# PowerModule.net
KiCad netlist of a schematic drawn in Altium Designer
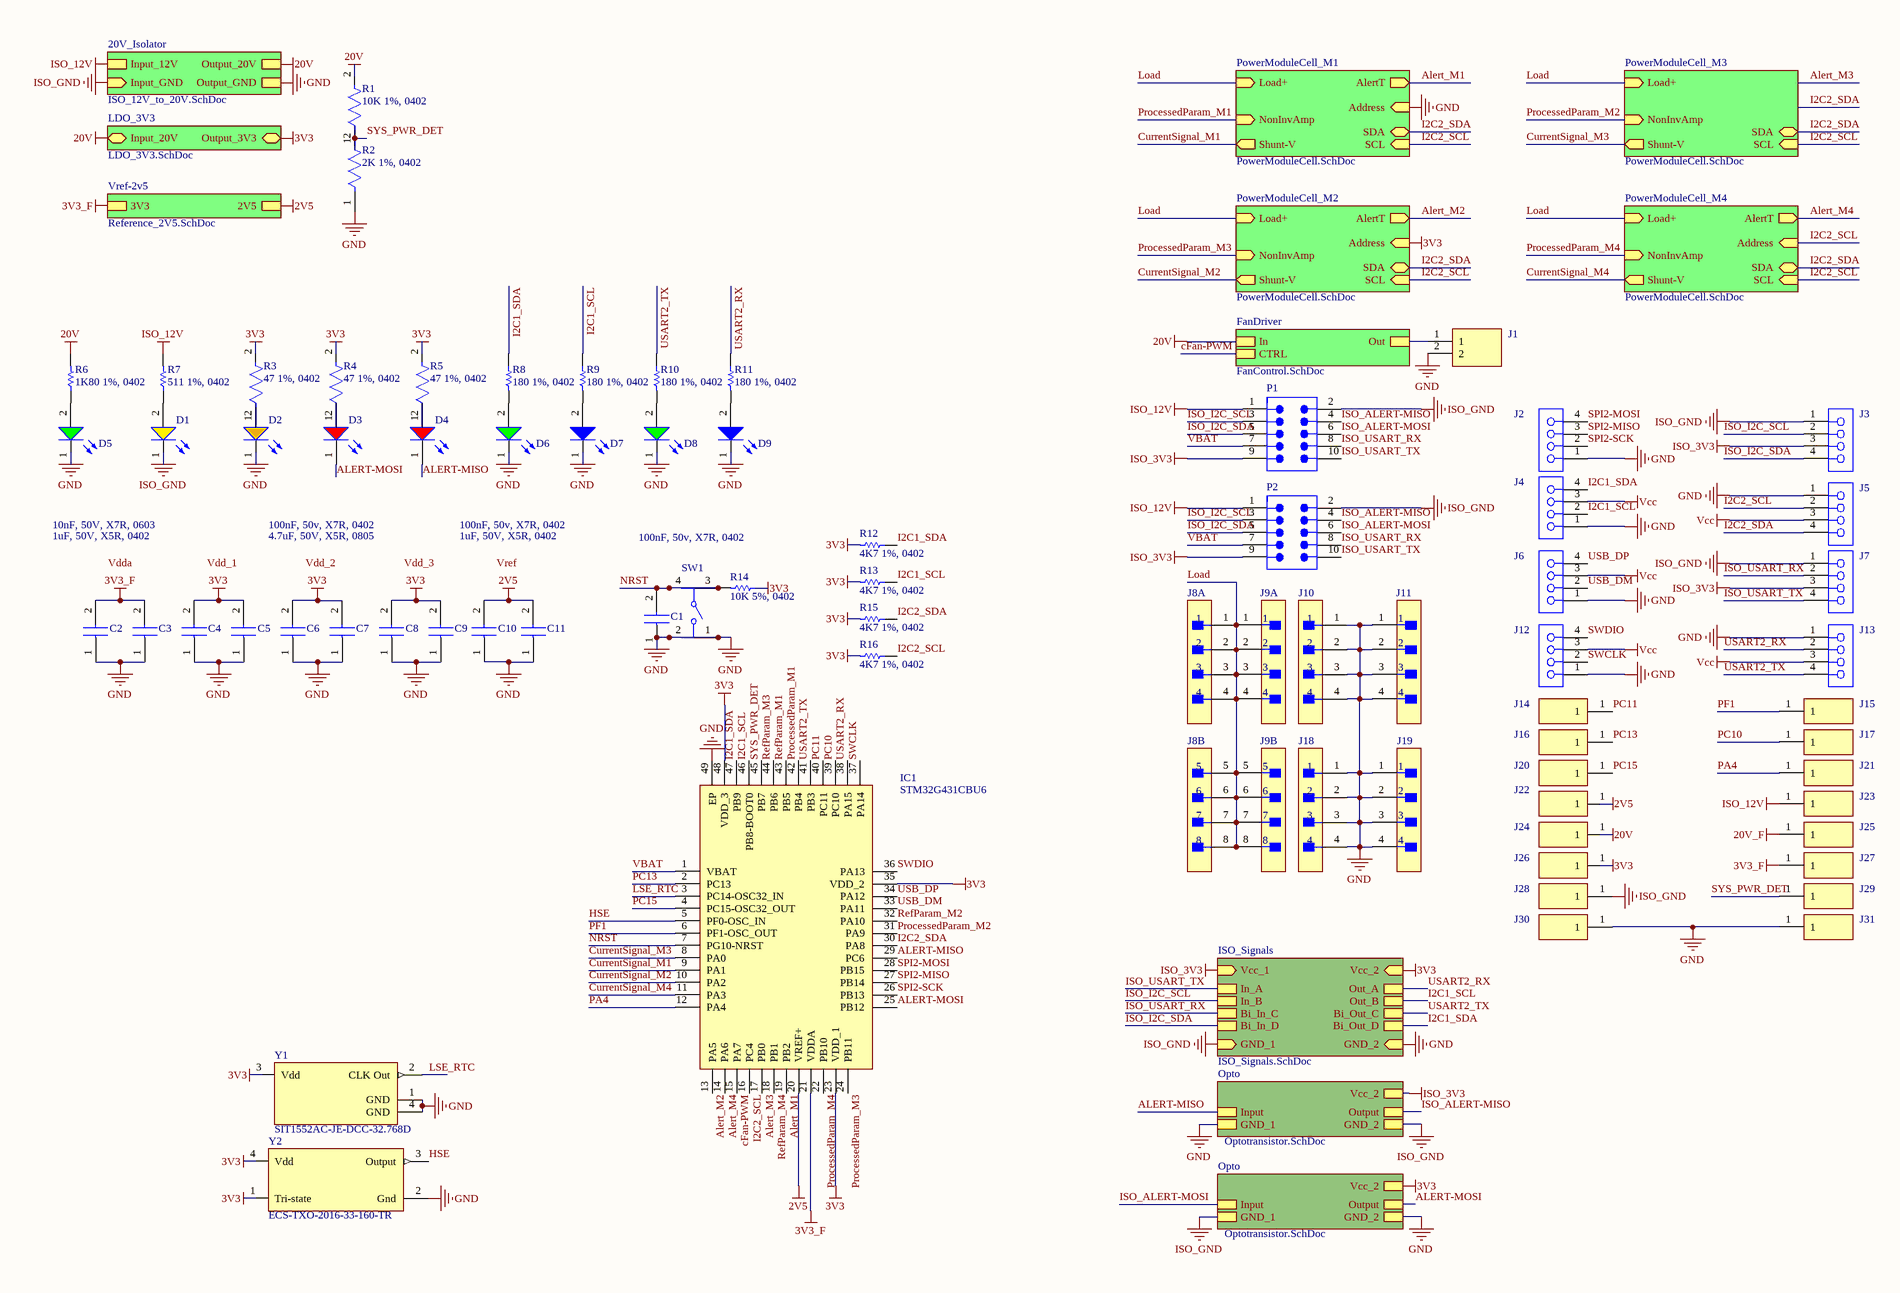
[diagram p0: PowerModule.SchDoc, left]
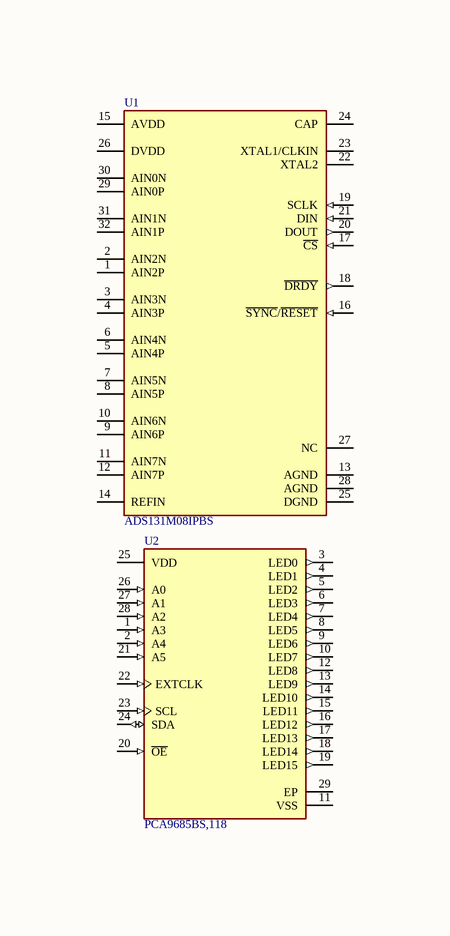
[diagram p1: PowerModule.SchDoc, middle]
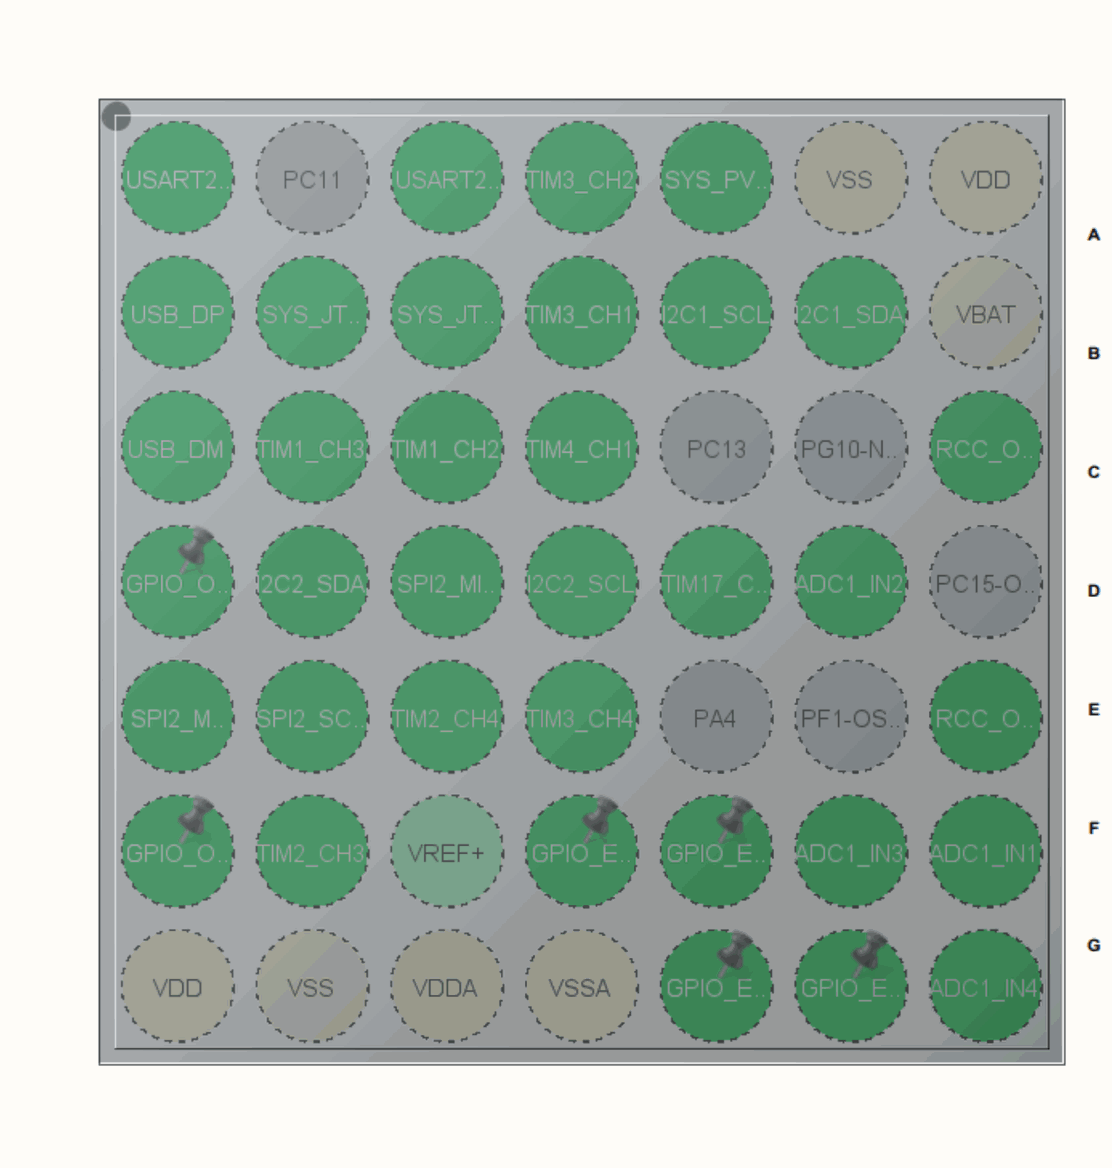
[diagram p2: PowerModule.SchDoc, right]

(export (version "E")
  (design (tool "Eeschema 10.0.6"))
  (components
    (comp (ref "C1")
      (value "100nF, 50v, X7R, 0402")
      (footprint "SamacSys:CAPC2012X88N")
      (description "Capacitor")
      (fields
        (field (name "MANUFACTURER_PART_NUMBER") "C0805C104M5RAC")
        (field (name "MOUSER PART NUMBER") "80-C0805C104M5RAC")
      )
      (libsource (lib "*") (part "C0805C104M5RAC"))
    )
    (comp (ref "C2")
      (value "10nF, 50V, X7R, 0603")
      (footprint "SamacSys:CAPC1608X87N")
      (description "Capacitor")
      (fields
        (field (name "MANUFACTURER_PART_NUMBER") "C0603C103J5RAC")
        (field (name "MOUSER PART NUMBER") "80-C0603C103J5RAC")
      )
      (libsource (lib "*") (part "C0603C103J5RAC"))
    )
    (comp (ref "C3")
      (value "1uF, 50V, X5R, 0402")
      (footprint "SamacSys:GRM15x")
      (description "Capacitor")
      (fields
        (field (name "MANUFACTURER_PART_NUMBER") "GRM155R61H105KE05J")
        (field (name "MOUSER PART NUMBER") "81-GRM155R61H105KE5J")
      )
      (libsource (lib "*") (part "GRM155R61H105KE05J"))
    )
    (comp (ref "C4")
      (value "100nF, 50v, X7R, 0402")
      (footprint "SamacSys:CAPC2012X88N")
      (description "Capacitor")
      (fields
        (field (name "MANUFACTURER_PART_NUMBER") "C0805C104M5RAC")
        (field (name "MOUSER PART NUMBER") "80-C0805C104M5RAC")
      )
      (libsource (lib "*") (part "C0805C104M5RAC"))
    )
    (comp (ref "C5")
      (value "4.7uF, 50V, X5R, 0805")
      (footprint "SamacSys:CAPC2012X145N")
      (description "Capacitor")
      (fields
        (field (name "MANUFACTURER_PART_NUMBER") "GRM21BR61H475ME51L")
        (field (name "MOUSER PART NUMBER") "81-GRM21BR61H475M51L")
      )
      (libsource (lib "*") (part "GRM21BR61H475ME51L"))
    )
    (comp (ref "C6")
      (value "100nF, 50v, X7R, 0402")
      (footprint "SamacSys:CAPC2012X88N")
      (description "Capacitor")
      (fields
        (field (name "MANUFACTURER_PART_NUMBER") "C0805C104M5RAC")
        (field (name "MOUSER PART NUMBER") "80-C0805C104M5RAC")
      )
      (libsource (lib "*") (part "C0805C104M5RAC"))
    )
    (comp (ref "C7")
      (value "4.7uF, 50V, X5R, 0805")
      (footprint "SamacSys:CAPC2012X145N")
      (description "Capacitor")
      (fields
        (field (name "MANUFACTURER_PART_NUMBER") "GRM21BR61H475ME51L")
        (field (name "MOUSER PART NUMBER") "81-GRM21BR61H475M51L")
      )
      (libsource (lib "*") (part "GRM21BR61H475ME51L"))
    )
    (comp (ref "C8")
      (value "100nF, 50v, X7R, 0402")
      (footprint "SamacSys:CAPC2012X88N")
      (description "Capacitor")
      (fields
        (field (name "MANUFACTURER_PART_NUMBER") "C0805C104M5RAC")
        (field (name "MOUSER PART NUMBER") "80-C0805C104M5RAC")
      )
      (libsource (lib "*") (part "C0805C104M5RAC"))
    )
    (comp (ref "C9")
      (value "4.7uF, 50V, X5R, 0805")
      (footprint "SamacSys:CAPC2012X145N")
      (description "Capacitor")
      (fields
        (field (name "MANUFACTURER_PART_NUMBER") "GRM21BR61H475ME51L")
        (field (name "MOUSER PART NUMBER") "81-GRM21BR61H475M51L")
      )
      (libsource (lib "*") (part "GRM21BR61H475ME51L"))
    )
    (comp (ref "C10")
      (value "100nF, 50v, X7R, 0402")
      (footprint "SamacSys:CAPC2012X88N")
      (description "Capacitor")
      (fields
        (field (name "MANUFACTURER_PART_NUMBER") "C0805C104M5RAC")
        (field (name "MOUSER PART NUMBER") "80-C0805C104M5RAC")
      )
      (libsource (lib "*") (part "C0805C104M5RAC"))
    )
    (comp (ref "C11")
      (value "1uF, 50V, X5R, 0402")
      (footprint "SamacSys:GRM15x")
      (description "Capacitor")
      (fields
        (field (name "MANUFACTURER_PART_NUMBER") "GRM155R61H105KE05J")
        (field (name "MOUSER PART NUMBER") "81-GRM155R61H105KE5J")
      )
      (libsource (lib "*") (part "GRM155R61H105KE05J"))
    )
    (comp (ref "D1")
      (value "150060YS75000")
      (footprint "WL-SMCW_0603_150060xx75000")
      (description "WL-SMCW SMT Mono-Color Chip LED Waterclear")
      (libsource (lib "Altium Content Vault") (part "LED_Yellow_2A-1K"))
    )
    (comp (ref "D2")
      (value "150060AS75000")
      (footprint "WL-SMCW_0603_150060xx75000")
      (description "WL-SMCW SMT Mono-Color Chip LED Waterclear")
      (libsource (lib "Altium Content Vault") (part "LED_Amber_2A-1K"))
    )
    (comp (ref "D3")
      (value "150060RS75000")
      (footprint "WL-SMCW_0603_150060xx75000")
      (description "LED Low-Power Uni-Color Red 630nm 2V 2-Pin Chip 0603(1608Metric) T/R")
      (libsource (lib "Altium Content Vault") (part "LED_Red_2A-1K"))
    )
    (comp (ref "D4")
      (value "150060RS75000")
      (footprint "WL-SMCW_0603_150060xx75000")
      (description "LED Low-Power Uni-Color Red 630nm 2V 2-Pin Chip 0603(1608Metric) T/R")
      (libsource (lib "Altium Content Vault") (part "LED_Red_2A-1K"))
    )
    (comp (ref "D5")
      (value "150060GS75000")
      (footprint "WL-SMCW_0603_150060xx75000")
      (description "430mcd Colorless transparence 520nm Emerald 140° LED0603 Light Emitting Diodes (LED) ROHS")
      (libsource (lib "Altium Content Vault") (part "LED_Green_2A-1K"))
    )
    (comp (ref "D6")
      (value "150060GS75000")
      (footprint "WL-SMCW_0603_150060xx75000")
      (description "430mcd Colorless transparence 520nm Emerald 140° LED0603 Light Emitting Diodes (LED) ROHS")
      (libsource (lib "Altium Content Vault") (part "LED_Green_2A-1K"))
    )
    (comp (ref "D7")
      (value "150060BS75000")
      (footprint "WL-SMCW_0603_150060xx75000")
      (description "Led, Blue, 470 Nm, 3.2 V, 30 Ma, 145 Mcd Rohs Compliant: Yes")
      (libsource (lib "Altium Content Vault") (part "LED_Blue_2A-1K"))
    )
    (comp (ref "D8")
      (value "150060GS75000")
      (footprint "WL-SMCW_0603_150060xx75000")
      (description "430mcd Colorless transparence 520nm Emerald 140° LED0603 Light Emitting Diodes (LED) ROHS")
      (libsource (lib "Altium Content Vault") (part "LED_Green_2A-1K"))
    )
    (comp (ref "D9")
      (value "150060BS75000")
      (footprint "WL-SMCW_0603_150060xx75000")
      (description "Led, Blue, 470 Nm, 3.2 V, 30 Ma, 145 Mcd Rohs Compliant: Yes")
      (libsource (lib "Altium Content Vault") (part "LED_Blue_2A-1K"))
    )
    (comp (ref "IC1")
      (value "STM32G431CBU6")
      (footprint "SamacSys:QFN50P700X700X65-49N-D")
      (description "Integrated Circuit")
      (fields (field (name "MOUSER PART NUMBER") "511-STM32G431CBU6"))
      (libsource (lib "*") (part "STM32G431CBU6"))
    )
    (comp (ref "J1")
      (value "1725656")
      (footprint "SamacSys:1725656")
      (description "Connector")
      (fields (field (name "MOUSER PART NUMBER") "651-1725656"))
      (libsource (lib "*") (part "1725656"))
    )
    (comp (ref "J2")
      (value "61300411821")
      (footprint "61300411821")
      (libsource (lib "Altium Content Vault") (part "Header_Female_1R_04P"))
    )
    (comp (ref "J3")
      (value "61300411821")
      (footprint "61300411821")
      (libsource (lib "Altium Content Vault") (part "Header_Female_1R_04P"))
    )
    (comp (ref "J4")
      (value "61300411821")
      (footprint "61300411821")
      (libsource (lib "Altium Content Vault") (part "Header_Female_1R_04P"))
    )
    (comp (ref "J5")
      (value "61300411821")
      (footprint "61300411821")
      (libsource (lib "Altium Content Vault") (part "Header_Female_1R_04P"))
    )
    (comp (ref "J6")
      (value "61300411821")
      (footprint "61300411821")
      (libsource (lib "Altium Content Vault") (part "Header_Female_1R_04P"))
    )
    (comp (ref "J7")
      (value "61300411821")
      (footprint "61300411821")
      (libsource (lib "Altium Content Vault") (part "Header_Female_1R_04P"))
    )
    (comp (ref "J8")
      (value "43045-0802")
      (footprint "FP-43045-0802-MFG")
      (description "CONN HEADER R/A 8POS 3MM")
      (libsource (lib "") (part "85438c39ca9ef07d43bb2e97c52bc44_1"))
    )
    (comp (ref "J9")
      (value "43045-0802")
      (footprint "FP-43045-0802-MFG")
      (description "CONN HEADER R/A 8POS 3MM")
      (libsource (lib "Altium Content Vault") (part "85438c39ca9ef07d43bb2e97c52bc44"))
    )
    (comp (ref "J10")
      (value "43045-0400")
      (footprint "FP-43045-0400-MFG")
      (description "CONN HEADER R/A 4POS 3MM")
      (fields
        (field (name "MANUFACTURER") "Molex")
        (field (name "OCTOPART") "https://octopart.com/43045-0400-molex-287063")
      )
      (libsource (lib "Altium Content Vault") (part "c01754ab0efc13afb7424b896f394ef"))
    )
    (comp (ref "J11")
      (value "43045-0400")
      (footprint "FP-43045-0400-MFG")
      (description "CONN HEADER R/A 4POS 3MM")
      (fields
        (field (name "MANUFACTURER") "Molex")
        (field (name "OCTOPART") "https://octopart.com/43045-0400-molex-287063")
      )
      (libsource (lib "") (part "c01754ab0efc13afb7424b896f394ef_1"))
    )
    (comp (ref "J12")
      (value "61300411821")
      (footprint "61300411821")
      (libsource (lib "Altium Content Vault") (part "Header_Female_1R_04P"))
    )
    (comp (ref "J13")
      (value "61300411821")
      (footprint "61300411821")
      (libsource (lib "Altium Content Vault") (part "Header_Female_1R_04P"))
    )
    (comp (ref "J14")
      (value "TestPad")
      (footprint "SamacSys:TestPad")
      (description "Connector")
      (fields
        (field (name "MANUFACTURER_PART_NUMBER") "61300111121")
        (field (name "MOUSER PART NUMBER") "710-61300111121")
      )
      (libsource (lib "") (part "61300111121_1"))
    )
    (comp (ref "J15")
      (value "TestPad")
      (footprint "SamacSys:TestPad")
      (description "Connector")
      (fields
        (field (name "MANUFACTURER_PART_NUMBER") "61300111121")
        (field (name "MOUSER PART NUMBER") "710-61300111121")
      )
      (libsource (lib "*") (part "61300111121"))
    )
    (comp (ref "J16")
      (value "TestPad")
      (footprint "SamacSys:TestPad")
      (description "Connector")
      (fields
        (field (name "MANUFACTURER_PART_NUMBER") "61300111121")
        (field (name "MOUSER PART NUMBER") "710-61300111121")
      )
      (libsource (lib "") (part "61300111121_1"))
    )
    (comp (ref "J17")
      (value "TestPad")
      (footprint "SamacSys:TestPad")
      (description "Connector")
      (fields
        (field (name "MANUFACTURER_PART_NUMBER") "61300111121")
        (field (name "MOUSER PART NUMBER") "710-61300111121")
      )
      (libsource (lib "*") (part "61300111121"))
    )
    (comp (ref "J18")
      (value "43045-0400")
      (footprint "FP-43045-0400-MFG")
      (description "CONN HEADER R/A 4POS 3MM")
      (fields
        (field (name "MANUFACTURER") "Molex")
        (field (name "OCTOPART") "https://octopart.com/43045-0400-molex-287063")
      )
      (libsource (lib "Altium Content Vault") (part "c01754ab0efc13afb7424b896f394ef"))
    )
    (comp (ref "J19")
      (value "43045-0400")
      (footprint "FP-43045-0400-MFG")
      (description "CONN HEADER R/A 4POS 3MM")
      (fields
        (field (name "MANUFACTURER") "Molex")
        (field (name "OCTOPART") "https://octopart.com/43045-0400-molex-287063")
      )
      (libsource (lib "") (part "c01754ab0efc13afb7424b896f394ef_1"))
    )
    (comp (ref "J20")
      (value "TestPad")
      (footprint "SamacSys:TestPad")
      (description "Connector")
      (fields
        (field (name "MANUFACTURER_PART_NUMBER") "61300111121")
        (field (name "MOUSER PART NUMBER") "710-61300111121")
      )
      (libsource (lib "") (part "61300111121_1"))
    )
    (comp (ref "J21")
      (value "TestPad")
      (footprint "SamacSys:TestPad")
      (description "Connector")
      (fields
        (field (name "MANUFACTURER_PART_NUMBER") "61300111121")
        (field (name "MOUSER PART NUMBER") "710-61300111121")
      )
      (libsource (lib "*") (part "61300111121"))
    )
    (comp (ref "J22")
      (value "TestPad")
      (footprint "SamacSys:TestPad")
      (description "Connector")
      (fields
        (field (name "MANUFACTURER_PART_NUMBER") "61300111121")
        (field (name "MOUSER PART NUMBER") "710-61300111121")
      )
      (libsource (lib "") (part "61300111121_1"))
    )
    (comp (ref "J23")
      (value "TestPad")
      (footprint "SamacSys:TestPad")
      (description "Connector")
      (fields
        (field (name "MANUFACTURER_PART_NUMBER") "61300111121")
        (field (name "MOUSER PART NUMBER") "710-61300111121")
      )
      (libsource (lib "*") (part "61300111121"))
    )
    (comp (ref "J24")
      (value "TestPad")
      (footprint "SamacSys:TestPad")
      (description "Connector")
      (fields
        (field (name "MANUFACTURER_PART_NUMBER") "61300111121")
        (field (name "MOUSER PART NUMBER") "710-61300111121")
      )
      (libsource (lib "") (part "61300111121_1"))
    )
    (comp (ref "J25")
      (value "TestPad")
      (footprint "SamacSys:TestPad")
      (description "Connector")
      (fields
        (field (name "MANUFACTURER_PART_NUMBER") "61300111121")
        (field (name "MOUSER PART NUMBER") "710-61300111121")
      )
      (libsource (lib "*") (part "61300111121"))
    )
    (comp (ref "J26")
      (value "TestPad")
      (footprint "SamacSys:TestPad")
      (description "Connector")
      (fields
        (field (name "MANUFACTURER_PART_NUMBER") "61300111121")
        (field (name "MOUSER PART NUMBER") "710-61300111121")
      )
      (libsource (lib "") (part "61300111121_1"))
    )
    (comp (ref "J27")
      (value "TestPad")
      (footprint "SamacSys:TestPad")
      (description "Connector")
      (fields
        (field (name "MANUFACTURER_PART_NUMBER") "61300111121")
        (field (name "MOUSER PART NUMBER") "710-61300111121")
      )
      (libsource (lib "*") (part "61300111121"))
    )
    (comp (ref "J28")
      (value "TestPad")
      (footprint "SamacSys:TestPad")
      (description "Connector")
      (fields
        (field (name "MANUFACTURER_PART_NUMBER") "61300111121")
        (field (name "MOUSER PART NUMBER") "710-61300111121")
      )
      (libsource (lib "") (part "61300111121_2"))
    )
    (comp (ref "J29")
      (value "TestPad")
      (footprint "SamacSys:TestPad")
      (description "Connector")
      (fields
        (field (name "MANUFACTURER_PART_NUMBER") "61300111121")
        (field (name "MOUSER PART NUMBER") "710-61300111121")
      )
      (libsource (lib "") (part "61300111121_3"))
    )
    (comp (ref "J30")
      (value "TestPad")
      (footprint "SamacSys:TestPad")
      (description "Connector")
      (fields
        (field (name "MANUFACTURER_PART_NUMBER") "61300111121")
        (field (name "MOUSER PART NUMBER") "710-61300111121")
      )
      (libsource (lib "") (part "61300111121_1"))
    )
    (comp (ref "J31")
      (value "TestPad")
      (footprint "SamacSys:TestPad")
      (description "Connector")
      (fields
        (field (name "MANUFACTURER_PART_NUMBER") "61300111121")
        (field (name "MOUSER PART NUMBER") "710-61300111121")
      )
      (libsource (lib "*") (part "61300111121"))
    )
    (comp (ref "P1")
      (value "61201021621")
      (footprint "61201021621")
      (libsource (lib "Altium Content Vault") (part "Header_Male_2R_10P"))
    )
    (comp (ref "P2")
      (value "61201021621")
      (footprint "61201021621")
      (libsource (lib "Altium Content Vault") (part "Header_Male_2R_10P"))
    )
    (comp (ref "R1")
      (value "10K 1%, 0402")
      (footprint "FP-ERA2A-MFG")
      (description "RES SMD 10K OHM 0.1% 1/16W 0402")
      (fields (field (name "TOLERANCE") "0.1%") (field (name "MANUFACTURER PART NUMBER") "ERA-2AEB103X"))
      (libsource (lib "Altium Content Vault") (part "1029c3af85768c4190bb7ad29bc67b5"))
    )
    (comp (ref "R2")
      (value "2K 1%, 0402")
      (footprint "FP-ERJ2RK-MFG")
      (description "RES SMD 2K OHM 1% 1/10W 0402")
      (fields (field (name "TOLERANCE") "1%"))
      (libsource (lib "Altium Content Vault") (part "1029c3af85768c4190bb7ad29bc67b5"))
    )
    (comp (ref "R3")
      (value "47 1%, 0402")
      (footprint "FP-ERJ2RK-IPC_C")
      (description "RES SMD 47 OHM 1% 1/10W 0402")
      (fields (field (name "TOLERANCE") "1%"))
      (libsource (lib "Altium Content Vault") (part "1029c3af85768c4190bb7ad29bc67b5"))
    )
    (comp (ref "R4")
      (value "47 1%, 0402")
      (footprint "FP-ERJ2RK-IPC_C")
      (description "RES SMD 47 OHM 1% 1/10W 0402")
      (fields (field (name "TOLERANCE") "1%"))
      (libsource (lib "Altium Content Vault") (part "1029c3af85768c4190bb7ad29bc67b5"))
    )
    (comp (ref "R5")
      (value "47 1%, 0402")
      (footprint "FP-ERJ2RK-IPC_C")
      (description "RES SMD 47 OHM 1% 1/10W 0402")
      (fields (field (name "TOLERANCE") "1%"))
      (libsource (lib "Altium Content Vault") (part "1029c3af85768c4190bb7ad29bc67b5"))
    )
    (comp (ref "R6")
      (value "1K80 1%, 0402")
      (footprint "RESC1005X40X25NL10T10")
      (fields (field (name "PART NUMBER") "ERA-2AED182X") (field (name "MANUFACTURER") "Panasonic"))
      (libsource (lib "Altium Content Vault") (part "RES"))
    )
    (comp (ref "R7")
      (value "511 1%, 0402")
      (footprint "RESC1005X40X25ML05T05")
      (fields (field (name "PART NUMBER") "ERJ-2RKF5113X") (field (name "MANUFACTURER") "Panasonic"))
      (libsource (lib "Altium Content Vault") (part "RES"))
    )
    (comp (ref "R8")
      (value "180 1%, 0402")
      (footprint "RESC1005X40X25NL05T05")
      (fields (field (name "MANUFACTURER") "Panasonic") (field (name "PART NUMBER") "ERJ2RKF1800X"))
      (libsource (lib "Altium Content Vault") (part "RES"))
    )
    (comp (ref "R9")
      (value "180 1%, 0402")
      (footprint "RESC1005X40X25NL05T05")
      (fields (field (name "MANUFACTURER") "Panasonic") (field (name "PART NUMBER") "ERJ2RKF1800X"))
      (libsource (lib "Altium Content Vault") (part "RES"))
    )
    (comp (ref "R10")
      (value "180 1%, 0402")
      (footprint "RESC1005X40X25NL05T05")
      (fields (field (name "MANUFACTURER") "Panasonic") (field (name "PART NUMBER") "ERJ2RKF1800X"))
      (libsource (lib "Altium Content Vault") (part "RES"))
    )
    (comp (ref "R11")
      (value "180 1%, 0402")
      (footprint "RESC1005X40X25NL05T05")
      (fields (field (name "MANUFACTURER") "Panasonic") (field (name "PART NUMBER") "ERJ2RKF1800X"))
      (libsource (lib "Altium Content Vault") (part "RES"))
    )
    (comp (ref "R12")
      (value "4K7 1%, 0402")
      (footprint "RESC1005X40X25LL05T05")
      (description "Chip Resistor, 4.7 KOhm, +/- 1%, 0.1 W, -55 to 155 degC, 0402 (1005 Metric), RoHS, Tape and Reel")
      (fields (field (name "TOLERANCE") "1%") (field (name "PARTNUMBER") "ERJ-2RKF4701X"))
      (libsource (lib "Altium Content Vault") (part "RES-2"))
    )
    (comp (ref "R13")
      (value "4K7 1%, 0402")
      (footprint "RESC1005X40X25LL05T05")
      (description "Chip Resistor, 4.7 KOhm, +/- 1%, 0.1 W, -55 to 155 degC, 0402 (1005 Metric), RoHS, Tape and Reel")
      (fields (field (name "TOLERANCE") "1%") (field (name "PARTNUMBER") "ERJ-2RKF4701X"))
      (libsource (lib "Altium Content Vault") (part "RES-2"))
    )
    (comp (ref "R14")
      (value "10K 5%, 0402")
      (footprint "RESC1005X40X25ML05T05")
      (fields (field (name "PART NUMBER") "ERJ-2GEJ103X") (field (name "MANUFACTURER") "Panasonic"))
      (libsource (lib "Altium Content Vault") (part "RES"))
    )
    (comp (ref "R15")
      (value "4K7 1%, 0402")
      (footprint "RESC1005X40X25LL05T05")
      (description "Chip Resistor, 4.7 KOhm, +/- 1%, 0.1 W, -55 to 155 degC, 0402 (1005 Metric), RoHS, Tape and Reel")
      (fields (field (name "TOLERANCE") "1%") (field (name "PARTNUMBER") "ERJ-2RKF4701X"))
      (libsource (lib "Altium Content Vault") (part "RES-2"))
    )
    (comp (ref "R16")
      (value "4K7 1%, 0402")
      (footprint "RESC1005X40X25LL05T05")
      (description "Chip Resistor, 4.7 KOhm, +/- 1%, 0.1 W, -55 to 155 degC, 0402 (1005 Metric), RoHS, Tape and Reel")
      (fields (field (name "TOLERANCE") "1%") (field (name "PARTNUMBER") "ERJ-2RKF4701X"))
      (libsource (lib "Altium Content Vault") (part "RES-2"))
    )
    (comp (ref "SW1")
      (value "PTS810SJM250SMTRLFS")
      (footprint "FP-PTS810SJM250SMTRLFS-MFG")
      (description "SWITCH TACTILE SPST-NO 0.05A 16V")
      (libsource (lib "Altium Content Vault") (part "1adf0dd01260c80cf25a44bfd6b99ba"))
    )
    (comp (ref "U1")
      (value "ADS131M08IPBS")
      (footprint "FP-PBS0032A-IPC_C")
      (description "8 CHANNEL 24 BIT SIMULTANEOUS SA")
      (libsource (lib "Altium Content Vault") (part "d3235cd83c76fd1a87a5b9f7ea79bfa"))
    )
    (comp (ref "U2")
      (value "PCA9685BS,118")
      (footprint "FP-SOT788-1-IPC_B")
      (description "IC LED DRVR LIN DIM 25MA 28HVQFN")
      (libsource (lib "Altium Content Vault") (part "09cd7da67ee680d27754e98215877c2"))
    )
    (comp (ref "Y1")
      (value "SIT1552AC-JE-DCC-32.768D")
      (footprint "FP-SiT1552-J-MFG")
      (description "MEMS OSC TCXO 32.7680KHZ LVCMOS")
      (libsource (lib "Altium Content Vault") (part "3465f1ec27570957a13575eae84d1d8"))
    )
    (comp (ref "Y2")
      (value "ECS-TXO-2016-33-160-TR")
      (footprint "FP-TXO-2016-MFG")
      (description "XTAL OSC TCXO 16MHZ 3.3V SMD")
      (fields
        (field (name "MANUFACTURER") "ECS")
        (field (name "OCTOPART") "https://octopart.com/ecs-txo-2016-33-160-tr-ecs+international-102811109")
      )
      (libsource (lib "Altium Content Vault") (part "79411a1daa27f0f3cdd4759ff5fa8e9"))
    )
  )
  (nets
    (net (code "1") (name "/ALERT-MISO") (class "Default")
      (node (ref "D4") (pin "1") (pinfunction "K_1") (pintype "passive"))
      (node (ref "IC1") (pin "29") (pinfunction "PC6_29") (pintype "passive"))
    )
    (net (code "2") (name "/ALERT-MOSI") (class "Default")
      (node (ref "D3") (pin "1") (pinfunction "K_1") (pintype "passive"))
      (node (ref "IC1") (pin "25") (pinfunction "PB12_25") (pintype "passive"))
    )
    (net (code "3") (name "/Alert_M1") (class "Default")
      (node (ref "IC1") (pin "19") (pinfunction "PB2_19") (pintype "passive"))
    )
    (net (code "4") (name "/Alert_M2") (class "Default")
      (node (ref "IC1") (pin "13") (pinfunction "PA5_13") (pintype "passive"))
    )
    (net (code "5") (name "/Alert_M3") (class "Default")
      (node (ref "IC1") (pin "17") (pinfunction "PB0_17") (pintype "passive"))
    )
    (net (code "6") (name "/Alert_M4") (class "Default")
      (node (ref "IC1") (pin "14") (pinfunction "PA6_14") (pintype "passive"))
    )
    (net (code "7") (name "/CurrentSignal_M1") (class "Default")
      (node (ref "IC1") (pin "9") (pinfunction "PA1_9") (pintype "passive"))
    )
    (net (code "8") (name "/CurrentSignal_M2") (class "Default")
      (node (ref "IC1") (pin "10") (pinfunction "PA2_10") (pintype "passive"))
    )
    (net (code "9") (name "/CurrentSignal_M3") (class "Default")
      (node (ref "IC1") (pin "8") (pinfunction "PA0_8") (pintype "passive"))
    )
    (net (code "10") (name "/CurrentSignal_M4") (class "Default")
      (node (ref "IC1") (pin "11") (pinfunction "PA3_11") (pintype "passive"))
    )
    (net (code "11") (name "/HSE") (class "Default")
      (node (ref "IC1") (pin "5") (pinfunction "PF0-OSC_IN_5") (pintype "passive"))
      (node (ref "Y2") (pin "3") (pinfunction "Output_3") (pintype "output"))
    )
    (net (code "12") (name "/I2C1_SCL") (class "Default")
      (node (ref "IC1") (pin "46") (pinfunction "PB8-BOOT0_46") (pintype "passive"))
      (node (ref "J4") (pin "2") (pinfunction "2_2") (pintype "passive"))
      (node (ref "R13") (pin "1") (pinfunction "1_1") (pintype "passive"))
      (node (ref "R9") (pin "1") (pinfunction "1_1") (pintype "passive"))
    )
    (net (code "13") (name "/I2C1_SDA") (class "Default")
      (node (ref "IC1") (pin "47") (pinfunction "PB9_47") (pintype "passive"))
      (node (ref "J4") (pin "4") (pinfunction "4_4") (pintype "passive"))
      (node (ref "R12") (pin "1") (pinfunction "1_1") (pintype "passive"))
      (node (ref "R8") (pin "1") (pinfunction "1_1") (pintype "passive"))
    )
    (net (code "14") (name "/I2C2_SCL") (class "Default")
      (node (ref "IC1") (pin "16") (pinfunction "PC4_16") (pintype "passive"))
      (node (ref "J5") (pin "2") (pinfunction "2_2") (pintype "passive"))
      (node (ref "R16") (pin "1") (pinfunction "1_1") (pintype "passive"))
    )
    (net (code "15") (name "/I2C2_SDA") (class "Default")
      (node (ref "IC1") (pin "30") (pinfunction "PA8_30") (pintype "passive"))
      (node (ref "J5") (pin "4") (pinfunction "4_4") (pintype "passive"))
      (node (ref "R15") (pin "1") (pinfunction "1_1") (pintype "passive"))
    )
    (net (code "16") (name "/ISO_ALERT-MISO") (class "Default")
      (node (ref "P1") (pin "4") (pinfunction "4_4") (pintype "passive"))
      (node (ref "P2") (pin "4") (pinfunction "4_4") (pintype "passive"))
    )
    (net (code "17") (name "/ISO_ALERT-MOSI") (class "Default")
      (node (ref "P1") (pin "6") (pinfunction "6_6") (pintype "passive"))
      (node (ref "P2") (pin "6") (pinfunction "6_6") (pintype "passive"))
    )
    (net (code "18") (name "/ISO_I2C_SCL") (class "Default")
      (node (ref "J3") (pin "2") (pinfunction "2_2") (pintype "passive"))
      (node (ref "P1") (pin "3") (pinfunction "3_3") (pintype "passive"))
      (node (ref "P2") (pin "3") (pinfunction "3_3") (pintype "passive"))
    )
    (net (code "19") (name "/ISO_I2C_SDA") (class "Default")
      (node (ref "J3") (pin "4") (pinfunction "4_4") (pintype "passive"))
      (node (ref "P1") (pin "5") (pinfunction "5_5") (pintype "passive"))
      (node (ref "P2") (pin "5") (pinfunction "5_5") (pintype "passive"))
    )
    (net (code "20") (name "/ISO_USART_RX") (class "Default")
      (node (ref "J7") (pin "2") (pinfunction "2_2") (pintype "passive"))
      (node (ref "P1") (pin "8") (pinfunction "8_8") (pintype "passive"))
      (node (ref "P2") (pin "8") (pinfunction "8_8") (pintype "passive"))
    )
    (net (code "21") (name "/ISO_USART_TX") (class "Default")
      (node (ref "J7") (pin "4") (pinfunction "4_4") (pintype "passive"))
      (node (ref "P1") (pin "10") (pinfunction "10_10") (pintype "passive"))
      (node (ref "P2") (pin "10") (pinfunction "10_10") (pintype "passive"))
    )
    (net (code "22") (name "/LSE_RTC") (class "Default")
      (node (ref "IC1") (pin "3") (pinfunction "PC14-OSC32_IN_3") (pintype "passive"))
      (node (ref "Y1") (pin "2") (pinfunction "CLK_Out_2") (pintype "output"))
    )
    (net (code "23") (name "/Load") (class "Default")
      (node (ref "J8") (pin "1") (pinfunction "1_1") (pintype "passive"))
      (node (ref "J8") (pin "2") (pinfunction "2_2") (pintype "passive"))
      (node (ref "J8") (pin "3") (pinfunction "3_3") (pintype "passive"))
      (node (ref "J8") (pin "4") (pinfunction "4_4") (pintype "passive"))
      (node (ref "J8") (pin "5") (pinfunction "5_5") (pintype "passive"))
      (node (ref "J8") (pin "6") (pinfunction "6_6") (pintype "passive"))
      (node (ref "J8") (pin "7") (pinfunction "7_7") (pintype "passive"))
      (node (ref "J8") (pin "8") (pinfunction "8_8") (pintype "passive"))
      (node (ref "J9") (pin "1") (pinfunction "1_1") (pintype "passive"))
      (node (ref "J9") (pin "2") (pinfunction "2_2") (pintype "passive"))
      (node (ref "J9") (pin "3") (pinfunction "3_3") (pintype "passive"))
      (node (ref "J9") (pin "4") (pinfunction "4_4") (pintype "passive"))
      (node (ref "J9") (pin "5") (pinfunction "5_5") (pintype "passive"))
      (node (ref "J9") (pin "6") (pinfunction "6_6") (pintype "passive"))
      (node (ref "J9") (pin "7") (pinfunction "7_7") (pintype "passive"))
      (node (ref "J9") (pin "8") (pinfunction "8_8") (pintype "passive"))
    )
    (net (code "24") (name "/NRST") (class "Default")
      (node (ref "C1") (pin "2") (pinfunction "2_2") (pintype "passive"))
      (node (ref "IC1") (pin "7") (pinfunction "PG10-NRST_7") (pintype "passive"))
      (node (ref "R14") (pin "2") (pinfunction "2_2") (pintype "passive"))
      (node (ref "SW1") (pin "3") (pinfunction "3_3") (pintype "passive"))
      (node (ref "SW1") (pin "4") (pinfunction "4_4") (pintype "passive"))
    )
    (net (code "25") (name "/Out") (class "Default")
      (node (ref "J1") (pin "1") (pinfunction "1_1") (pintype "passive"))
    )
    (net (code "26") (name "/PA4") (class "Default")
      (node (ref "IC1") (pin "12") (pinfunction "PA4_12") (pintype "passive"))
      (node (ref "J21") (pin "1") (pinfunction "1_1") (pintype "passive"))
    )
    (net (code "27") (name "/PC10") (class "Default")
      (node (ref "IC1") (pin "39") (pinfunction "PC10_39") (pintype "passive"))
      (node (ref "J17") (pin "1") (pinfunction "1_1") (pintype "passive"))
    )
    (net (code "28") (name "/PC11") (class "Default")
      (node (ref "IC1") (pin "40") (pinfunction "PC11_40") (pintype "passive"))
      (node (ref "J14") (pin "1") (pinfunction "1_1") (pintype "passive"))
    )
    (net (code "29") (name "/PC13") (class "Default")
      (node (ref "IC1") (pin "2") (pinfunction "PC13_2") (pintype "passive"))
      (node (ref "J16") (pin "1") (pinfunction "1_1") (pintype "passive"))
    )
    (net (code "30") (name "/PC15") (class "Default")
      (node (ref "IC1") (pin "4") (pinfunction "PC15-OSC32_OUT_4") (pintype "passive"))
      (node (ref "J20") (pin "1") (pinfunction "1_1") (pintype "passive"))
    )
    (net (code "31") (name "/PF1") (class "Default")
      (node (ref "IC1") (pin "6") (pinfunction "PF1-OSC_OUT_6") (pintype "passive"))
      (node (ref "J15") (pin "1") (pinfunction "1_1") (pintype "passive"))
    )
    (net (code "32") (name "/ProcessedParam_M1") (class "Default")
      (node (ref "IC1") (pin "42") (pinfunction "PB4_42") (pintype "passive"))
    )
    (net (code "33") (name "/ProcessedParam_M2") (class "Default")
      (node (ref "IC1") (pin "31") (pinfunction "PA9_31") (pintype "passive"))
    )
    (net (code "34") (name "/ProcessedParam_M3") (class "Default")
      (node (ref "IC1") (pin "24") (pinfunction "PB11_24") (pintype "passive"))
    )
    (net (code "35") (name "/ProcessedParam_M4") (class "Default")
      (node (ref "IC1") (pin "22") (pinfunction "PB10_22") (pintype "passive"))
    )
    (net (code "36") (name "/RefParam_M1") (class "Default")
      (node (ref "IC1") (pin "43") (pinfunction "PB5_43") (pintype "passive"))
    )
    (net (code "37") (name "/RefParam_M2") (class "Default")
      (node (ref "IC1") (pin "32") (pinfunction "PA10_32") (pintype "passive"))
    )
    (net (code "38") (name "/RefParam_M3") (class "Default")
      (node (ref "IC1") (pin "44") (pinfunction "PB6_44") (pintype "passive"))
    )
    (net (code "39") (name "/RefParam_M4") (class "Default")
      (node (ref "IC1") (pin "18") (pinfunction "PB1_18") (pintype "passive"))
    )
    (net (code "40") (name "/SPI2-MISO") (class "Default")
      (node (ref "IC1") (pin "27") (pinfunction "PB14_27") (pintype "passive"))
      (node (ref "J2") (pin "3") (pinfunction "3_3") (pintype "passive"))
    )
    (net (code "41") (name "/SPI2-MOSI") (class "Default")
      (node (ref "IC1") (pin "28") (pinfunction "PB15_28") (pintype "passive"))
      (node (ref "J2") (pin "4") (pinfunction "4_4") (pintype "passive"))
    )
    (net (code "42") (name "/SPI2-SCK") (class "Default")
      (node (ref "IC1") (pin "26") (pinfunction "PB13_26") (pintype "passive"))
      (node (ref "J2") (pin "2") (pinfunction "2_2") (pintype "passive"))
    )
    (net (code "43") (name "/SWCLK") (class "Default")
      (node (ref "IC1") (pin "37") (pinfunction "PA14_37") (pintype "passive"))
      (node (ref "J12") (pin "2") (pinfunction "2_2") (pintype "passive"))
    )
    (net (code "44") (name "/SWDIO") (class "Default")
      (node (ref "IC1") (pin "36") (pinfunction "PA13_36") (pintype "passive"))
      (node (ref "J12") (pin "4") (pinfunction "4_4") (pintype "passive"))
    )
    (net (code "45") (name "/SYS_PWR_DET") (class "Default")
      (node (ref "IC1") (pin "45") (pinfunction "PB7_45") (pintype "passive"))
      (node (ref "J29") (pin "1") (pinfunction "1_1") (pintype "passive"))
      (node (ref "R1") (pin "1") (pinfunction "1_1") (pintype "passive"))
      (node (ref "R2") (pin "2") (pinfunction "2_2") (pintype "passive"))
    )
    (net (code "46") (name "/USART2_RX") (class "Default")
      (node (ref "IC1") (pin "38") (pinfunction "PA15_38") (pintype "passive"))
      (node (ref "J13") (pin "2") (pinfunction "2_2") (pintype "passive"))
      (node (ref "R11") (pin "1") (pinfunction "1_1") (pintype "passive"))
    )
    (net (code "47") (name "/USART2_TX") (class "Default")
      (node (ref "IC1") (pin "41") (pinfunction "PB3_41") (pintype "passive"))
      (node (ref "J13") (pin "4") (pinfunction "4_4") (pintype "passive"))
      (node (ref "R10") (pin "1") (pinfunction "1_1") (pintype "passive"))
    )
    (net (code "48") (name "/USB_DM") (class "Default")
      (node (ref "IC1") (pin "33") (pinfunction "PA11_33") (pintype "passive"))
      (node (ref "J6") (pin "2") (pinfunction "2_2") (pintype "passive"))
    )
    (net (code "49") (name "/USB_DP") (class "Default")
      (node (ref "IC1") (pin "34") (pinfunction "PA12_34") (pintype "passive"))
      (node (ref "J6") (pin "4") (pinfunction "4_4") (pintype "passive"))
    )
    (net (code "50") (name "/VBAT") (class "Default")
      (node (ref "IC1") (pin "1") (pinfunction "VBAT_1") (pintype "passive"))
      (node (ref "P1") (pin "7") (pinfunction "7_7") (pintype "passive"))
      (node (ref "P2") (pin "7") (pinfunction "7_7") (pintype "passive"))
    )
    (net (code "51") (name "/cFan-PWM") (class "Default")
      (node (ref "IC1") (pin "15") (pinfunction "PA7_15") (pintype "passive"))
    )
    (net (code "52") (name "2V5") (class "Default")
      (node (ref "C10") (pin "2") (pinfunction "2_2") (pintype "passive"))
      (node (ref "C11") (pin "2") (pinfunction "2_2") (pintype "passive"))
      (node (ref "IC1") (pin "20") (pinfunction "VREF+_20") (pintype "passive"))
      (node (ref "J22") (pin "1") (pinfunction "1_1") (pintype "passive"))
    )
    (net (code "53") (name "3V3") (class "Default")
      (node (ref "C4") (pin "2") (pinfunction "2_2") (pintype "passive"))
      (node (ref "C5") (pin "2") (pinfunction "2_2") (pintype "passive"))
      (node (ref "C6") (pin "2") (pinfunction "2_2") (pintype "passive"))
      (node (ref "C7") (pin "2") (pinfunction "2_2") (pintype "passive"))
      (node (ref "C8") (pin "2") (pinfunction "2_2") (pintype "passive"))
      (node (ref "C9") (pin "2") (pinfunction "2_2") (pintype "passive"))
      (node (ref "IC1") (pin "23") (pinfunction "VDD_1_23") (pintype "passive"))
      (node (ref "IC1") (pin "35") (pinfunction "VDD_2_35") (pintype "passive"))
      (node (ref "IC1") (pin "48") (pinfunction "VDD_3_48") (pintype "passive"))
      (node (ref "J26") (pin "1") (pinfunction "1_1") (pintype "passive"))
      (node (ref "R12") (pin "2") (pinfunction "2_2") (pintype "passive"))
      (node (ref "R13") (pin "2") (pinfunction "2_2") (pintype "passive"))
      (node (ref "R14") (pin "1") (pinfunction "1_1") (pintype "passive"))
      (node (ref "R15") (pin "2") (pinfunction "2_2") (pintype "passive"))
      (node (ref "R16") (pin "2") (pinfunction "2_2") (pintype "passive"))
      (node (ref "R3") (pin "2") (pinfunction "2_2") (pintype "passive"))
      (node (ref "R4") (pin "2") (pinfunction "2_2") (pintype "passive"))
      (node (ref "R5") (pin "2") (pinfunction "2_2") (pintype "passive"))
      (node (ref "Y1") (pin "3") (pinfunction "Vdd_3") (pintype "power_in"))
      (node (ref "Y2") (pin "1") (pinfunction "Tri-state_1") (pintype "passive"))
      (node (ref "Y2") (pin "4") (pinfunction "Vdd_4") (pintype "power_in"))
    )
    (net (code "54") (name "3V3_F") (class "Default")
      (node (ref "C2") (pin "2") (pinfunction "2_2") (pintype "passive"))
      (node (ref "C3") (pin "2") (pinfunction "2_2") (pintype "passive"))
      (node (ref "IC1") (pin "21") (pinfunction "VDDA_21") (pintype "passive"))
      (node (ref "J27") (pin "1") (pinfunction "1_1") (pintype "passive"))
    )
    (net (code "55") (name "20V") (class "Default")
      (node (ref "J24") (pin "1") (pinfunction "1_1") (pintype "passive"))
      (node (ref "R1") (pin "2") (pinfunction "2_2") (pintype "passive"))
      (node (ref "R6") (pin "2") (pinfunction "2_2") (pintype "passive"))
    )
    (net (code "56") (name "20V_F") (class "Default")
      (node (ref "J25") (pin "1") (pinfunction "1_1") (pintype "passive"))
    )
    (net (code "57") (name "GND") (class "Default")
      (node (ref "C1") (pin "1") (pinfunction "1_1") (pintype "passive"))
      (node (ref "C10") (pin "1") (pinfunction "1_1") (pintype "passive"))
      (node (ref "C11") (pin "1") (pinfunction "1_1") (pintype "passive"))
      (node (ref "C2") (pin "1") (pinfunction "1_1") (pintype "passive"))
      (node (ref "C3") (pin "1") (pinfunction "1_1") (pintype "passive"))
      (node (ref "C4") (pin "1") (pinfunction "1_1") (pintype "passive"))
      (node (ref "C5") (pin "1") (pinfunction "1_1") (pintype "passive"))
      (node (ref "C6") (pin "1") (pinfunction "1_1") (pintype "passive"))
      (node (ref "C7") (pin "1") (pinfunction "1_1") (pintype "passive"))
      (node (ref "C8") (pin "1") (pinfunction "1_1") (pintype "passive"))
      (node (ref "C9") (pin "1") (pinfunction "1_1") (pintype "passive"))
      (node (ref "D2") (pin "1") (pinfunction "K_1") (pintype "passive"))
      (node (ref "D5") (pin "1") (pinfunction "K_1") (pintype "passive"))
      (node (ref "D6") (pin "1") (pinfunction "K_1") (pintype "passive"))
      (node (ref "D7") (pin "1") (pinfunction "K_1") (pintype "passive"))
      (node (ref "D8") (pin "1") (pinfunction "K_1") (pintype "passive"))
      (node (ref "D9") (pin "1") (pinfunction "K_1") (pintype "passive"))
      (node (ref "IC1") (pin "49") (pinfunction "EP_49") (pintype "passive"))
      (node (ref "J1") (pin "2") (pinfunction "2_2") (pintype "passive"))
      (node (ref "J10") (pin "1") (pinfunction "1_1") (pintype "passive"))
      (node (ref "J10") (pin "2") (pinfunction "2_2") (pintype "passive"))
      (node (ref "J10") (pin "3") (pinfunction "3_3") (pintype "passive"))
      (node (ref "J10") (pin "4") (pinfunction "4_4") (pintype "passive"))
      (node (ref "J11") (pin "1") (pinfunction "1_1") (pintype "passive"))
      (node (ref "J11") (pin "2") (pinfunction "2_2") (pintype "passive"))
      (node (ref "J11") (pin "3") (pinfunction "3_3") (pintype "passive"))
      (node (ref "J11") (pin "4") (pinfunction "4_4") (pintype "passive"))
      (node (ref "J12") (pin "1") (pinfunction "1_1") (pintype "passive"))
      (node (ref "J13") (pin "1") (pinfunction "1_1") (pintype "passive"))
      (node (ref "J18") (pin "1") (pinfunction "1_1") (pintype "passive"))
      (node (ref "J18") (pin "2") (pinfunction "2_2") (pintype "passive"))
      (node (ref "J18") (pin "3") (pinfunction "3_3") (pintype "passive"))
      (node (ref "J18") (pin "4") (pinfunction "4_4") (pintype "passive"))
      (node (ref "J19") (pin "1") (pinfunction "1_1") (pintype "passive"))
      (node (ref "J19") (pin "2") (pinfunction "2_2") (pintype "passive"))
      (node (ref "J19") (pin "3") (pinfunction "3_3") (pintype "passive"))
      (node (ref "J19") (pin "4") (pinfunction "4_4") (pintype "passive"))
      (node (ref "J2") (pin "1") (pinfunction "1_1") (pintype "passive"))
      (node (ref "J30") (pin "1") (pinfunction "1_1") (pintype "passive"))
      (node (ref "J31") (pin "1") (pinfunction "1_1") (pintype "passive"))
      (node (ref "J4") (pin "1") (pinfunction "1_1") (pintype "passive"))
      (node (ref "J5") (pin "1") (pinfunction "1_1") (pintype "passive"))
      (node (ref "J6") (pin "1") (pinfunction "1_1") (pintype "passive"))
      (node (ref "R2") (pin "1") (pinfunction "1_1") (pintype "passive"))
      (node (ref "SW1") (pin "1") (pinfunction "1_1") (pintype "passive"))
      (node (ref "SW1") (pin "2") (pinfunction "2_2") (pintype "passive"))
      (node (ref "Y1") (pin "1") (pinfunction "GND_1") (pintype "power_in"))
      (node (ref "Y1") (pin "4") (pinfunction "GND_4") (pintype "power_in"))
      (node (ref "Y2") (pin "2") (pinfunction "Gnd_2") (pintype "power_in"))
    )
    (net (code "58") (name "ISO_3V3") (class "Default")
      (node (ref "J3") (pin "3") (pinfunction "3_3") (pintype "passive"))
      (node (ref "J7") (pin "3") (pinfunction "3_3") (pintype "passive"))
      (node (ref "P1") (pin "9") (pinfunction "9_9") (pintype "passive"))
      (node (ref "P2") (pin "9") (pinfunction "9_9") (pintype "passive"))
    )
    (net (code "59") (name "ISO_12V") (class "Default")
      (node (ref "J23") (pin "1") (pinfunction "1_1") (pintype "passive"))
      (node (ref "P1") (pin "1") (pinfunction "1_1") (pintype "passive"))
      (node (ref "P2") (pin "1") (pinfunction "1_1") (pintype "passive"))
      (node (ref "R7") (pin "2") (pinfunction "2_2") (pintype "passive"))
    )
    (net (code "60") (name "ISO_GND") (class "Default")
      (node (ref "D1") (pin "1") (pinfunction "K_1") (pintype "passive"))
      (node (ref "J28") (pin "1") (pinfunction "1_1") (pintype "passive"))
      (node (ref "J3") (pin "1") (pinfunction "1_1") (pintype "passive"))
      (node (ref "J7") (pin "1") (pinfunction "1_1") (pintype "passive"))
      (node (ref "P1") (pin "2") (pinfunction "2_2") (pintype "passive"))
      (node (ref "P2") (pin "2") (pinfunction "2_2") (pintype "passive"))
    )
    (net (code "61") (name "Net-(D1-A)") (class "Default")
      (node (ref "D1") (pin "2") (pinfunction "A_2") (pintype "passive"))
      (node (ref "R7") (pin "1") (pinfunction "1_1") (pintype "passive"))
    )
    (net (code "62") (name "Net-(D2-A)") (class "Default")
      (node (ref "D2") (pin "2") (pinfunction "A_2") (pintype "passive"))
      (node (ref "R3") (pin "1") (pinfunction "1_1") (pintype "passive"))
    )
    (net (code "63") (name "Net-(D3-A)") (class "Default")
      (node (ref "D3") (pin "2") (pinfunction "A_2") (pintype "passive"))
      (node (ref "R4") (pin "1") (pinfunction "1_1") (pintype "passive"))
    )
    (net (code "64") (name "Net-(D4-A)") (class "Default")
      (node (ref "D4") (pin "2") (pinfunction "A_2") (pintype "passive"))
      (node (ref "R5") (pin "1") (pinfunction "1_1") (pintype "passive"))
    )
    (net (code "65") (name "Net-(D5-A)") (class "Default")
      (node (ref "D5") (pin "2") (pinfunction "A_2") (pintype "passive"))
      (node (ref "R6") (pin "1") (pinfunction "1_1") (pintype "passive"))
    )
    (net (code "66") (name "Net-(D6-A)") (class "Default")
      (node (ref "D6") (pin "2") (pinfunction "A_2") (pintype "passive"))
      (node (ref "R8") (pin "2") (pinfunction "2_2") (pintype "passive"))
    )
    (net (code "67") (name "Net-(D7-A)") (class "Default")
      (node (ref "D7") (pin "2") (pinfunction "A_2") (pintype "passive"))
      (node (ref "R9") (pin "2") (pinfunction "2_2") (pintype "passive"))
    )
    (net (code "68") (name "Net-(D8-A)") (class "Default")
      (node (ref "D8") (pin "2") (pinfunction "A_2") (pintype "passive"))
      (node (ref "R10") (pin "2") (pinfunction "2_2") (pintype "passive"))
    )
    (net (code "69") (name "Net-(D9-A)") (class "Default")
      (node (ref "D9") (pin "2") (pinfunction "A_2") (pintype "passive"))
      (node (ref "R11") (pin "2") (pinfunction "2_2") (pintype "passive"))
    )
    (net (code "70") (name "Vcc") (class "Default")
      (node (ref "J12") (pin "3") (pinfunction "3_3") (pintype "passive"))
      (node (ref "J13") (pin "3") (pinfunction "3_3") (pintype "passive"))
      (node (ref "J4") (pin "3") (pinfunction "3_3") (pintype "passive"))
      (node (ref "J5") (pin "3") (pinfunction "3_3") (pintype "passive"))
      (node (ref "J6") (pin "3") (pinfunction "3_3") (pintype "passive"))
    )
    (net (code "71") (name "unconnected-(U1-AGND-Pad13)") (class "Default")
      (node (ref "U1") (pin "13") (pinfunction "AGND_13") (pintype "power_in"))
    )
    (net (code "72") (name "unconnected-(U1-AGND-Pad28)") (class "Default")
      (node (ref "U1") (pin "28") (pinfunction "AGND_28") (pintype "power_in"))
    )
    (net (code "73") (name "unconnected-(U1-AIN0N-Pad30)") (class "Default")
      (node (ref "U1") (pin "30") (pinfunction "AIN0N_30") (pintype "passive"))
    )
    (net (code "74") (name "unconnected-(U1-AIN0P-Pad29)") (class "Default")
      (node (ref "U1") (pin "29") (pinfunction "AIN0P_29") (pintype "passive"))
    )
    (net (code "75") (name "unconnected-(U1-AIN1N-Pad31)") (class "Default")
      (node (ref "U1") (pin "31") (pinfunction "AIN1N_31") (pintype "passive"))
    )
    (net (code "76") (name "unconnected-(U1-AIN1P-Pad32)") (class "Default")
      (node (ref "U1") (pin "32") (pinfunction "AIN1P_32") (pintype "passive"))
    )
    (net (code "77") (name "unconnected-(U1-AIN2N-Pad2)") (class "Default")
      (node (ref "U1") (pin "2") (pinfunction "AIN2N_2") (pintype "passive"))
    )
    (net (code "78") (name "unconnected-(U1-AIN2P-Pad1)") (class "Default")
      (node (ref "U1") (pin "1") (pinfunction "AIN2P_1") (pintype "passive"))
    )
    (net (code "79") (name "unconnected-(U1-AIN3N-Pad3)") (class "Default")
      (node (ref "U1") (pin "3") (pinfunction "AIN3N_3") (pintype "passive"))
    )
    (net (code "80") (name "unconnected-(U1-AIN3P-Pad4)") (class "Default")
      (node (ref "U1") (pin "4") (pinfunction "AIN3P_4") (pintype "passive"))
    )
    (net (code "81") (name "unconnected-(U1-AIN4N-Pad6)") (class "Default")
      (node (ref "U1") (pin "6") (pinfunction "AIN4N_6") (pintype "passive"))
    )
    (net (code "82") (name "unconnected-(U1-AIN4P-Pad5)") (class "Default")
      (node (ref "U1") (pin "5") (pinfunction "AIN4P_5") (pintype "passive"))
    )
    (net (code "83") (name "unconnected-(U1-AIN5N-Pad7)") (class "Default")
      (node (ref "U1") (pin "7") (pinfunction "AIN5N_7") (pintype "passive"))
    )
    (net (code "84") (name "unconnected-(U1-AIN5P-Pad8)") (class "Default")
      (node (ref "U1") (pin "8") (pinfunction "AIN5P_8") (pintype "passive"))
    )
    (net (code "85") (name "unconnected-(U1-AIN6N-Pad10)") (class "Default")
      (node (ref "U1") (pin "10") (pinfunction "AIN6N_10") (pintype "passive"))
    )
    (net (code "86") (name "unconnected-(U1-AIN6P-Pad9)") (class "Default")
      (node (ref "U1") (pin "9") (pinfunction "AIN6P_9") (pintype "passive"))
    )
    (net (code "87") (name "unconnected-(U1-AIN7N-Pad11)") (class "Default")
      (node (ref "U1") (pin "11") (pinfunction "AIN7N_11") (pintype "passive"))
    )
    (net (code "88") (name "unconnected-(U1-AIN7P-Pad12)") (class "Default")
      (node (ref "U1") (pin "12") (pinfunction "AIN7P_12") (pintype "passive"))
    )
    (net (code "89") (name "unconnected-(U1-AVDD-Pad15)") (class "Default")
      (node (ref "U1") (pin "15") (pinfunction "AVDD_15") (pintype "power_in"))
    )
    (net (code "90") (name "unconnected-(U1-CAP-Pad24)") (class "Default")
      (node (ref "U1") (pin "24") (pinfunction "CAP_24") (pintype "passive"))
    )
    (net (code "91") (name "unconnected-(U1-DGND-Pad25)") (class "Default")
      (node (ref "U1") (pin "25") (pinfunction "DGND_25") (pintype "power_in"))
    )
    (net (code "92") (name "unconnected-(U1-DIN-Pad21)") (class "Default")
      (node (ref "U1") (pin "21") (pinfunction "DIN_21") (pintype "input"))
    )
    (net (code "93") (name "unconnected-(U1-DOUT-Pad20)") (class "Default")
      (node (ref "U1") (pin "20") (pinfunction "DOUT_20") (pintype "output"))
    )
    (net (code "94") (name "unconnected-(U1-DVDD-Pad26)") (class "Default")
      (node (ref "U1") (pin "26") (pinfunction "DVDD_26") (pintype "power_in"))
    )
    (net (code "95") (name "unconnected-(U1-NC-Pad27)") (class "Default")
      (node (ref "U1") (pin "27") (pinfunction "NC_27") (pintype "passive"))
    )
    (net (code "96") (name "unconnected-(U1-REFIN-Pad14)") (class "Default")
      (node (ref "U1") (pin "14") (pinfunction "REFIN_14") (pintype "passive"))
    )
    (net (code "97") (name "unconnected-(U1-SCLK-Pad19)") (class "Default")
      (node (ref "U1") (pin "19") (pinfunction "SCLK_19") (pintype "input"))
    )
    (net (code "98") (name "unconnected-(U1-XTAL1{slash}CLKIN-Pad23)") (class "Default")
      (node (ref "U1") (pin "23") (pinfunction "XTAL1/CLKIN_23") (pintype "passive"))
    )
    (net (code "99") (name "unconnected-(U1-XTAL2-Pad22)") (class "Default")
      (node (ref "U1") (pin "22") (pinfunction "XTAL2_22") (pintype "passive"))
    )
    (net (code "100") (name "unconnected-(U1-~{CS}-Pad17)") (class "Default")
      (node (ref "U1") (pin "17") (pinfunction "~{CS}_17") (pintype "input"))
    )
    (net (code "101") (name "unconnected-(U1-~{DRDY}-Pad18)") (class "Default")
      (node (ref "U1") (pin "18") (pinfunction "~{DRDY}_18") (pintype "output"))
    )
    (net (code "102") (name "unconnected-(U1-~{SYNC}{slash}~{RESET}-Pad16)") (class "Default")
      (node (ref "U1") (pin "16") (pinfunction "~{SYNC}/~{RESET}_16") (pintype "input"))
    )
    (net (code "103") (name "unconnected-(U2-A0-Pad26)") (class "Default")
      (node (ref "U2") (pin "26") (pinfunction "A0_26") (pintype "input"))
    )
    (net (code "104") (name "unconnected-(U2-A1-Pad27)") (class "Default")
      (node (ref "U2") (pin "27") (pinfunction "A1_27") (pintype "input"))
    )
    (net (code "105") (name "unconnected-(U2-A2-Pad28)") (class "Default")
      (node (ref "U2") (pin "28") (pinfunction "A2_28") (pintype "input"))
    )
    (net (code "106") (name "unconnected-(U2-A3-Pad1)") (class "Default")
      (node (ref "U2") (pin "1") (pinfunction "A3_1") (pintype "input"))
    )
    (net (code "107") (name "unconnected-(U2-A4-Pad2)") (class "Default")
      (node (ref "U2") (pin "2") (pinfunction "A4_2") (pintype "input"))
    )
    (net (code "108") (name "unconnected-(U2-A5-Pad21)") (class "Default")
      (node (ref "U2") (pin "21") (pinfunction "A5_21") (pintype "input"))
    )
    (net (code "109") (name "unconnected-(U2-EP-Pad29)") (class "Default")
      (node (ref "U2") (pin "29") (pinfunction "EP_29") (pintype "passive"))
    )
    (net (code "110") (name "unconnected-(U2-EXTCLK-Pad22)") (class "Default")
      (node (ref "U2") (pin "22") (pinfunction "EXTCLK_22") (pintype "input"))
    )
    (net (code "111") (name "unconnected-(U2-LED0-Pad3)") (class "Default")
      (node (ref "U2") (pin "3") (pinfunction "LED0_3") (pintype "output"))
    )
    (net (code "112") (name "unconnected-(U2-LED1-Pad4)") (class "Default")
      (node (ref "U2") (pin "4") (pinfunction "LED1_4") (pintype "output"))
    )
    (net (code "113") (name "unconnected-(U2-LED2-Pad5)") (class "Default")
      (node (ref "U2") (pin "5") (pinfunction "LED2_5") (pintype "output"))
    )
    (net (code "114") (name "unconnected-(U2-LED3-Pad6)") (class "Default")
      (node (ref "U2") (pin "6") (pinfunction "LED3_6") (pintype "output"))
    )
    (net (code "115") (name "unconnected-(U2-LED4-Pad7)") (class "Default")
      (node (ref "U2") (pin "7") (pinfunction "LED4_7") (pintype "output"))
    )
    (net (code "116") (name "unconnected-(U2-LED5-Pad8)") (class "Default")
      (node (ref "U2") (pin "8") (pinfunction "LED5_8") (pintype "output"))
    )
    (net (code "117") (name "unconnected-(U2-LED6-Pad9)") (class "Default")
      (node (ref "U2") (pin "9") (pinfunction "LED6_9") (pintype "output"))
    )
    (net (code "118") (name "unconnected-(U2-LED7-Pad10)") (class "Default")
      (node (ref "U2") (pin "10") (pinfunction "LED7_10") (pintype "output"))
    )
    (net (code "119") (name "unconnected-(U2-LED8-Pad12)") (class "Default")
      (node (ref "U2") (pin "12") (pinfunction "LED8_12") (pintype "output"))
    )
    (net (code "120") (name "unconnected-(U2-LED9-Pad13)") (class "Default")
      (node (ref "U2") (pin "13") (pinfunction "LED9_13") (pintype "output"))
    )
    (net (code "121") (name "unconnected-(U2-LED10-Pad14)") (class "Default")
      (node (ref "U2") (pin "14") (pinfunction "LED10_14") (pintype "output"))
    )
    (net (code "122") (name "unconnected-(U2-LED11-Pad15)") (class "Default")
      (node (ref "U2") (pin "15") (pinfunction "LED11_15") (pintype "output"))
    )
    (net (code "123") (name "unconnected-(U2-LED12-Pad16)") (class "Default")
      (node (ref "U2") (pin "16") (pinfunction "LED12_16") (pintype "output"))
    )
    (net (code "124") (name "unconnected-(U2-LED13-Pad17)") (class "Default")
      (node (ref "U2") (pin "17") (pinfunction "LED13_17") (pintype "output"))
    )
    (net (code "125") (name "unconnected-(U2-LED14-Pad18)") (class "Default")
      (node (ref "U2") (pin "18") (pinfunction "LED14_18") (pintype "output"))
    )
    (net (code "126") (name "unconnected-(U2-LED15-Pad19)") (class "Default")
      (node (ref "U2") (pin "19") (pinfunction "LED15_19") (pintype "output"))
    )
    (net (code "127") (name "unconnected-(U2-SCL-Pad23)") (class "Default")
      (node (ref "U2") (pin "23") (pinfunction "SCL_23") (pintype "input"))
    )
    (net (code "128") (name "unconnected-(U2-SDA-Pad24)") (class "Default")
      (node (ref "U2") (pin "24") (pinfunction "SDA_24") (pintype "bidirectional"))
    )
    (net (code "129") (name "unconnected-(U2-VDD-Pad25)") (class "Default")
      (node (ref "U2") (pin "25") (pinfunction "VDD_25") (pintype "power_in"))
    )
    (net (code "130") (name "unconnected-(U2-VSS-Pad11)") (class "Default")
      (node (ref "U2") (pin "11") (pinfunction "VSS_11") (pintype "power_in"))
    )
    (net (code "131") (name "unconnected-(U2-~{OE}-Pad20)") (class "Default")
      (node (ref "U2") (pin "20") (pinfunction "~{OE}_20") (pintype "input"))
    )
  )
)
